# tdz.net
KiCad netlist of a schematic drawn in EAGLE
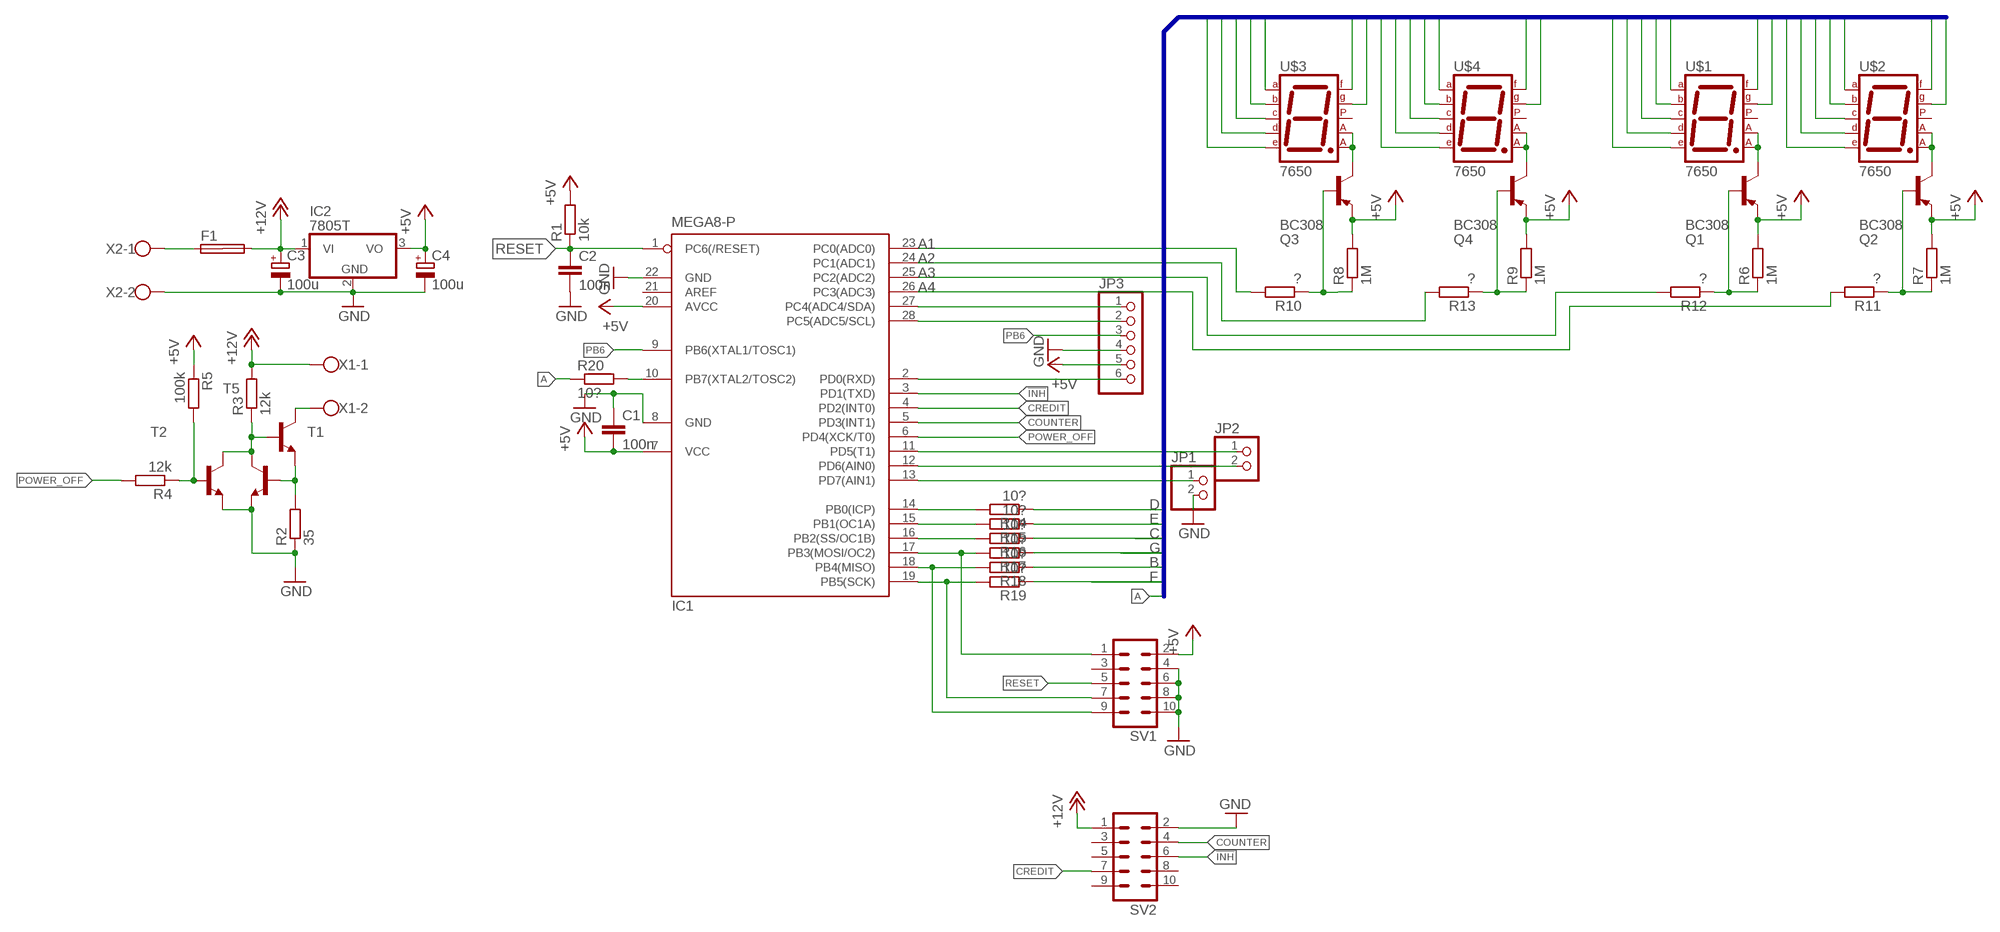
[diagram p0: schematic, sheet 1]

(export (version "E")
  (design (tool "Eeschema 10.0.6"))
  (components
    (comp (ref "C1")
      (value "100n")
      (footprint "eagle-import:C0603")
      (libsource (lib "eagle-import") (part "C-EUC0603"))
    )
    (comp (ref "C2")
      (value "100n")
      (footprint "eagle-import:C0603")
      (libsource (lib "eagle-import") (part "C-EUC0603"))
    )
    (comp (ref "C3")
      (value "100u")
      (footprint "eagle-import:E22-9")
      (libsource (lib "eagle-import") (part "CPOL-EUE22-9AXIAL"))
    )
    (comp (ref "C4")
      (value "100u")
      (footprint "eagle-import:E22-9")
      (libsource (lib "eagle-import") (part "CPOL-EUE22-9AXIAL"))
    )
    (comp (ref "F1")
      (value "SHK20Q")
      (footprint "eagle-import:SHK20Q")
      (libsource (lib "eagle-import") (part "SHK20Q"))
    )
    (comp (ref "IC1")
      (value "MEGA8-P")
      (footprint "eagle-import:DIL28-3")
      (libsource (lib "eagle-import") (part "MEGA8-P"))
    )
    (comp (ref "IC2")
      (value "7805T")
      (footprint "eagle-import:TO220H")
      (libsource (lib "eagle-import") (part "78T05"))
    )
    (comp (ref "JP1")
      (value "PINHD-1X02_2.54-S")
      (footprint "eagle-import:1X02-S")
      (libsource (lib "eagle-import") (part "PINHD-1X02_2.54-S"))
    )
    (comp (ref "JP2")
      (value "PINHD-1X02_2.54-S")
      (footprint "eagle-import:1X02-S")
      (libsource (lib "eagle-import") (part "PINHD-1X02_2.54-S"))
    )
    (comp (ref "JP3")
      (value "PINHD-1X6")
      (footprint "eagle-import:1X06")
      (libsource (lib "eagle-import") (part "PINHD-1X6"))
    )
    (comp (ref "Q1")
      (value "BC308")
      (footprint "eagle-import:TO92-EBC")
      (libsource (lib "eagle-import") (part "BCX79"))
    )
    (comp (ref "Q2")
      (value "BC308")
      (footprint "eagle-import:TO92-EBC")
      (libsource (lib "eagle-import") (part "BCX79"))
    )
    (comp (ref "Q3")
      (value "BC308")
      (footprint "eagle-import:TO92-EBC")
      (libsource (lib "eagle-import") (part "BCX79"))
    )
    (comp (ref "Q4")
      (value "BC308")
      (footprint "eagle-import:TO92-EBC")
      (libsource (lib "eagle-import") (part "BCX79"))
    )
    (comp (ref "R1")
      (value "10k")
      (footprint "eagle-import:R0603")
      (libsource (lib "eagle-import") (part "R-EU_R0603"))
    )
    (comp (ref "R2")
      (value "35")
      (footprint "eagle-import:R0603")
      (libsource (lib "eagle-import") (part "R-EU_R0603"))
    )
    (comp (ref "R3")
      (value "12k")
      (footprint "eagle-import:R0603")
      (libsource (lib "eagle-import") (part "R-EU_R0603"))
    )
    (comp (ref "R4")
      (value "12k")
      (footprint "eagle-import:R0603")
      (libsource (lib "eagle-import") (part "R-EU_R0603"))
    )
    (comp (ref "R5")
      (value "100k")
      (footprint "eagle-import:R0603")
      (libsource (lib "eagle-import") (part "R-EU_R0603"))
    )
    (comp (ref "R6")
      (value "1M")
      (footprint "eagle-import:R0603")
      (libsource (lib "eagle-import") (part "R-EU_R0603"))
    )
    (comp (ref "R7")
      (value "1M")
      (footprint "eagle-import:R0603")
      (libsource (lib "eagle-import") (part "R-EU_R0603"))
    )
    (comp (ref "R8")
      (value "1M")
      (footprint "eagle-import:R0603")
      (libsource (lib "eagle-import") (part "R-EU_R0603"))
    )
    (comp (ref "R9")
      (value "1M")
      (footprint "eagle-import:R0603")
      (libsource (lib "eagle-import") (part "R-EU_R0603"))
    )
    (comp (ref "R10")
      (value "?")
      (footprint "eagle-import:0207_7")
      (libsource (lib "eagle-import") (part "R-EU_0207/7"))
    )
    (comp (ref "R11")
      (value "?")
      (footprint "eagle-import:0207_7")
      (libsource (lib "eagle-import") (part "R-EU_0207/7"))
    )
    (comp (ref "R12")
      (value "?")
      (footprint "eagle-import:0207_7")
      (libsource (lib "eagle-import") (part "R-EU_0207/7"))
    )
    (comp (ref "R13")
      (value "?")
      (footprint "eagle-import:0207_7")
      (libsource (lib "eagle-import") (part "R-EU_0207/7"))
    )
    (comp (ref "R14")
      (value "10?")
      (footprint "eagle-import:R0603")
      (libsource (lib "eagle-import") (part "R-EU_R0603"))
    )
    (comp (ref "R15")
      (value "10?")
      (footprint "eagle-import:R0603")
      (libsource (lib "eagle-import") (part "R-EU_R0603"))
    )
    (comp (ref "R16")
      (value "10?")
      (footprint "eagle-import:R0603")
      (libsource (lib "eagle-import") (part "R-EU_R0603"))
    )
    (comp (ref "R17")
      (value "10?")
      (footprint "eagle-import:R0603")
      (libsource (lib "eagle-import") (part "R-EU_R0603"))
    )
    (comp (ref "R18")
      (value "10?")
      (footprint "eagle-import:R0603")
      (libsource (lib "eagle-import") (part "R-EU_R0603"))
    )
    (comp (ref "R19")
      (value "10?")
      (footprint "eagle-import:R0603")
      (libsource (lib "eagle-import") (part "R-EU_R0603"))
    )
    (comp (ref "R20")
      (value "10?")
      (footprint "eagle-import:R0603")
      (libsource (lib "eagle-import") (part "R-EU_R0603"))
    )
    (comp (ref "SV1")
      (value "ML10L")
      (footprint "eagle-import:ML10L")
      (libsource (lib "eagle-import") (part "ML10L"))
    )
    (comp (ref "SV2")
      (value "ML10L")
      (footprint "eagle-import:ML10L")
      (libsource (lib "eagle-import") (part "ML10L"))
    )
    (comp (ref "T1")
      (value "BC548-NPN-TO92-CBE")
      (footprint "eagle-import:TO92-CBE")
      (libsource (lib "eagle-import") (part "-NPN-TO92-CBEBC548"))
    )
    (comp (ref "T2")
      (value "BC548-NPN-TO92-CBE")
      (footprint "eagle-import:TO92-CBE")
      (libsource (lib "eagle-import") (part "-NPN-TO92-CBEBC548"))
    )
    (comp (ref "T5")
      (value "BC548-NPN-TO92-CBE")
      (footprint "eagle-import:TO92-CBE")
      (libsource (lib "eagle-import") (part "-NPN-TO92-CBEBC548"))
    )
    (comp (ref "U$1")
      (value "7650")
      (footprint "eagle-import:7650")
      (libsource (lib "eagle-import") (part "7650"))
    )
    (comp (ref "U$2")
      (value "7650")
      (footprint "eagle-import:7650")
      (libsource (lib "eagle-import") (part "7650"))
    )
    (comp (ref "U$3")
      (value "7650")
      (footprint "eagle-import:7650")
      (libsource (lib "eagle-import") (part "7650"))
    )
    (comp (ref "U$4")
      (value "7650")
      (footprint "eagle-import:7650")
      (libsource (lib "eagle-import") (part "7650"))
    )
    (comp (ref "X1")
      (value "W237-102")
      (footprint "eagle-import:W237-102")
      (libsource (lib "eagle-import") (part "W237-102"))
    )
    (comp (ref "X2")
      (value "W237-102")
      (footprint "eagle-import:W237-102")
      (libsource (lib "eagle-import") (part "W237-102"))
    )
  )
  (nets
    (net (code "1") (name "+5V") (class "Default")
      (node (ref "C1") (pin "2") (pinfunction "2_2") (pintype "passive"))
      (node (ref "C4") (pin "+") (pinfunction "+_+") (pintype "passive"))
      (node (ref "IC1") (pin "20") (pinfunction "AVCC_20") (pintype "power_in"))
      (node (ref "IC1") (pin "7") (pinfunction "VCC_7") (pintype "power_in"))
      (node (ref "IC2") (pin "3") (pinfunction "VO_3") (pintype "passive"))
      (node (ref "JP3") (pin "5") (pinfunction "5_5") (pintype "passive"))
      (node (ref "Q1") (pin "E") (pinfunction "E_E") (pintype "passive"))
      (node (ref "Q2") (pin "E") (pinfunction "E_E") (pintype "passive"))
      (node (ref "Q3") (pin "E") (pinfunction "E_E") (pintype "passive"))
      (node (ref "Q4") (pin "E") (pinfunction "E_E") (pintype "passive"))
      (node (ref "R1") (pin "2") (pinfunction "2_2") (pintype "passive"))
      (node (ref "R5") (pin "1") (pinfunction "1_1") (pintype "passive"))
      (node (ref "R6") (pin "2") (pinfunction "2_2") (pintype "passive"))
      (node (ref "R7") (pin "2") (pinfunction "2_2") (pintype "passive"))
      (node (ref "R8") (pin "2") (pinfunction "2_2") (pintype "passive"))
      (node (ref "R9") (pin "2") (pinfunction "2_2") (pintype "passive"))
      (node (ref "SV1") (pin "2") (pinfunction "2_2") (pintype "passive"))
    )
    (net (code "2") (name "+12V") (class "Default")
      (node (ref "C3") (pin "+") (pinfunction "+_+") (pintype "passive"))
      (node (ref "F1") (pin "2A") (pinfunction "2A_2A") (pintype "passive"))
      (node (ref "IC2") (pin "1") (pinfunction "VI_1") (pintype "input"))
      (node (ref "R3") (pin "2") (pinfunction "2_2") (pintype "passive"))
      (node (ref "SV2") (pin "1") (pinfunction "1_1") (pintype "passive"))
      (node (ref "X1") (pin "1") (pinfunction "KL_1") (pintype "passive"))
    )
    (net (code "3") (name "/A1") (class "Default")
      (node (ref "IC1") (pin "23") (pinfunction "PC0(ADC0)_23") (pintype "bidirectional"))
      (node (ref "R10") (pin "2") (pinfunction "2_2") (pintype "passive"))
    )
    (net (code "4") (name "/A2") (class "Default")
      (node (ref "IC1") (pin "24") (pinfunction "PC1(ADC1)_24") (pintype "bidirectional"))
      (node (ref "R13") (pin "2") (pinfunction "2_2") (pintype "passive"))
    )
    (net (code "5") (name "/A3") (class "Default")
      (node (ref "IC1") (pin "25") (pinfunction "PC2(ADC2)_25") (pintype "bidirectional"))
      (node (ref "R12") (pin "2") (pinfunction "2_2") (pintype "passive"))
    )
    (net (code "6") (name "/A4") (class "Default")
      (node (ref "IC1") (pin "26") (pinfunction "PC3(ADC3)_26") (pintype "bidirectional"))
      (node (ref "R11") (pin "2") (pinfunction "2_2") (pintype "passive"))
    )
    (net (code "7") (name "/B") (class "Default")
      (node (ref "R18") (pin "1") (pinfunction "1_1") (pintype "passive"))
      (node (ref "U$1") (pin "P$13") (pinfunction "B_P$13") (pintype "passive"))
      (node (ref "U$2") (pin "P$13") (pinfunction "B_P$13") (pintype "passive"))
      (node (ref "U$3") (pin "P$13") (pinfunction "B_P$13") (pintype "passive"))
      (node (ref "U$4") (pin "P$13") (pinfunction "B_P$13") (pintype "passive"))
    )
    (net (code "8") (name "/C") (class "Default")
      (node (ref "R16") (pin "1") (pinfunction "1_1") (pintype "passive"))
      (node (ref "U$1") (pin "P$10") (pinfunction "C_P$10") (pintype "passive"))
      (node (ref "U$2") (pin "P$10") (pinfunction "C_P$10") (pintype "passive"))
      (node (ref "U$3") (pin "P$10") (pinfunction "C_P$10") (pintype "passive"))
      (node (ref "U$4") (pin "P$10") (pinfunction "C_P$10") (pintype "passive"))
    )
    (net (code "9") (name "/D") (class "Default")
      (node (ref "R14") (pin "1") (pinfunction "1_1") (pintype "passive"))
      (node (ref "U$1") (pin "P$8") (pinfunction "D_P$8") (pintype "passive"))
      (node (ref "U$2") (pin "P$8") (pinfunction "D_P$8") (pintype "passive"))
      (node (ref "U$3") (pin "P$8") (pinfunction "D_P$8") (pintype "passive"))
      (node (ref "U$4") (pin "P$8") (pinfunction "D_P$8") (pintype "passive"))
    )
    (net (code "10") (name "/E") (class "Default")
      (node (ref "R15") (pin "1") (pinfunction "1_1") (pintype "passive"))
      (node (ref "U$1") (pin "P$7") (pinfunction "E_P$7") (pintype "passive"))
      (node (ref "U$2") (pin "P$7") (pinfunction "E_P$7") (pintype "passive"))
      (node (ref "U$3") (pin "P$7") (pinfunction "E_P$7") (pintype "passive"))
      (node (ref "U$4") (pin "P$7") (pinfunction "E_P$7") (pintype "passive"))
    )
    (net (code "11") (name "/F") (class "Default")
      (node (ref "R19") (pin "1") (pinfunction "1_1") (pintype "passive"))
      (node (ref "U$1") (pin "P$2") (pinfunction "F_P$2") (pintype "passive"))
      (node (ref "U$2") (pin "P$2") (pinfunction "F_P$2") (pintype "passive"))
      (node (ref "U$3") (pin "P$2") (pinfunction "F_P$2") (pintype "passive"))
      (node (ref "U$4") (pin "P$2") (pinfunction "F_P$2") (pintype "passive"))
    )
    (net (code "12") (name "/G") (class "Default")
      (node (ref "R17") (pin "1") (pinfunction "1_1") (pintype "passive"))
      (node (ref "U$1") (pin "P$11") (pinfunction "G_P$11") (pintype "passive"))
      (node (ref "U$2") (pin "P$11") (pinfunction "G_P$11") (pintype "passive"))
      (node (ref "U$3") (pin "P$11") (pinfunction "G_P$11") (pintype "passive"))
      (node (ref "U$4") (pin "P$11") (pinfunction "G_P$11") (pintype "passive"))
    )
    (net (code "13") (name "/~{INH}") (class "Default")
      (node (ref "IC1") (pin "3") (pinfunction "PD1(TXD)_3") (pintype "bidirectional"))
      (node (ref "SV2") (pin "6") (pinfunction "6_6") (pintype "passive"))
    )
    (net (code "14") (name "A") (class "Default")
      (node (ref "R20") (pin "1") (pinfunction "1_1") (pintype "passive"))
      (node (ref "U$1") (pin "P$1") (pinfunction "A_P$1") (pintype "passive"))
      (node (ref "U$2") (pin "P$1") (pinfunction "A_P$1") (pintype "passive"))
      (node (ref "U$3") (pin "P$1") (pinfunction "A_P$1") (pintype "passive"))
      (node (ref "U$4") (pin "P$1") (pinfunction "A_P$1") (pintype "passive"))
    )
    (net (code "15") (name "COUNTER") (class "Default")
      (node (ref "IC1") (pin "5") (pinfunction "PD3(INT1)_5") (pintype "bidirectional"))
      (node (ref "SV2") (pin "4") (pinfunction "4_4") (pintype "passive"))
    )
    (net (code "16") (name "CREDIT") (class "Default")
      (node (ref "IC1") (pin "4") (pinfunction "PD2(INT0)_4") (pintype "bidirectional"))
      (node (ref "SV2") (pin "7") (pinfunction "7_7") (pintype "passive"))
    )
    (net (code "17") (name "GND") (class "Default")
      (node (ref "C1") (pin "1") (pinfunction "1_1") (pintype "passive"))
      (node (ref "C2") (pin "2") (pinfunction "2_2") (pintype "passive"))
      (node (ref "C3") (pin "-") (pinfunction "-_-") (pintype "passive"))
      (node (ref "C4") (pin "-") (pinfunction "-_-") (pintype "passive"))
      (node (ref "IC1") (pin "22") (pinfunction "GND_22") (pintype "power_in"))
      (node (ref "IC1") (pin "8") (pinfunction "GND_8") (pintype "power_in"))
      (node (ref "IC2") (pin "2") (pinfunction "GND_2") (pintype "passive"))
      (node (ref "JP1") (pin "2") (pinfunction "2_2") (pintype "passive"))
      (node (ref "JP3") (pin "4") (pinfunction "4_4") (pintype "passive"))
      (node (ref "R2") (pin "1") (pinfunction "1_1") (pintype "passive"))
      (node (ref "SV1") (pin "10") (pinfunction "10_10") (pintype "passive"))
      (node (ref "SV1") (pin "4") (pinfunction "4_4") (pintype "passive"))
      (node (ref "SV1") (pin "6") (pinfunction "6_6") (pintype "passive"))
      (node (ref "SV1") (pin "8") (pinfunction "8_8") (pintype "passive"))
      (node (ref "SV2") (pin "2") (pinfunction "2_2") (pintype "passive"))
      (node (ref "T1") (pin "E") (pinfunction "E_E") (pintype "passive"))
      (node (ref "T2") (pin "E") (pinfunction "E_E") (pintype "passive"))
      (node (ref "X2") (pin "2") (pinfunction "KL_2") (pintype "passive"))
    )
    (net (code "18") (name "Net-(IC1-PB0(ICP))") (class "Default")
      (node (ref "IC1") (pin "14") (pinfunction "PB0(ICP)_14") (pintype "bidirectional"))
      (node (ref "R14") (pin "2") (pinfunction "2_2") (pintype "passive"))
    )
    (net (code "19") (name "Net-(IC1-PB1(OC1A))") (class "Default")
      (node (ref "IC1") (pin "15") (pinfunction "PB1(OC1A)_15") (pintype "bidirectional"))
      (node (ref "R15") (pin "2") (pinfunction "2_2") (pintype "passive"))
    )
    (net (code "20") (name "Net-(IC1-PB2(SS{slash}OC1B))") (class "Default")
      (node (ref "IC1") (pin "16") (pinfunction "PB2(SS/OC1B)_16") (pintype "bidirectional"))
      (node (ref "R16") (pin "2") (pinfunction "2_2") (pintype "passive"))
    )
    (net (code "21") (name "Net-(IC1-PB3(MOSI{slash}OC2))") (class "Default")
      (node (ref "IC1") (pin "17") (pinfunction "PB3(MOSI/OC2)_17") (pintype "bidirectional"))
      (node (ref "R17") (pin "2") (pinfunction "2_2") (pintype "passive"))
      (node (ref "SV1") (pin "1") (pinfunction "1_1") (pintype "passive"))
    )
    (net (code "22") (name "Net-(IC1-PB4(MISO))") (class "Default")
      (node (ref "IC1") (pin "18") (pinfunction "PB4(MISO)_18") (pintype "bidirectional"))
      (node (ref "R18") (pin "2") (pinfunction "2_2") (pintype "passive"))
      (node (ref "SV1") (pin "9") (pinfunction "9_9") (pintype "passive"))
    )
    (net (code "23") (name "Net-(IC1-PB5(SCK))") (class "Default")
      (node (ref "IC1") (pin "19") (pinfunction "PB5(SCK)_19") (pintype "bidirectional"))
      (node (ref "R19") (pin "2") (pinfunction "2_2") (pintype "passive"))
      (node (ref "SV1") (pin "7") (pinfunction "7_7") (pintype "passive"))
    )
    (net (code "24") (name "Net-(IC1-PB7(XTAL2{slash}TOSC2))") (class "Default")
      (node (ref "IC1") (pin "10") (pinfunction "PB7(XTAL2/TOSC2)_10") (pintype "bidirectional"))
      (node (ref "R20") (pin "2") (pinfunction "2_2") (pintype "passive"))
    )
    (net (code "25") (name "Net-(IC1-PC4(ADC4{slash}SDA))") (class "Default")
      (node (ref "IC1") (pin "27") (pinfunction "PC4(ADC4/SDA)_27") (pintype "bidirectional"))
      (node (ref "JP3") (pin "1") (pinfunction "1_1") (pintype "passive"))
    )
    (net (code "26") (name "Net-(IC1-PC5(ADC5{slash}SCL))") (class "Default")
      (node (ref "IC1") (pin "28") (pinfunction "PC5(ADC5/SCL)_28") (pintype "bidirectional"))
      (node (ref "JP3") (pin "2") (pinfunction "2_2") (pintype "passive"))
    )
    (net (code "27") (name "Net-(IC1-PD0(RXD))") (class "Default")
      (node (ref "IC1") (pin "2") (pinfunction "PD0(RXD)_2") (pintype "bidirectional"))
      (node (ref "JP3") (pin "6") (pinfunction "6_6") (pintype "passive"))
    )
    (net (code "28") (name "Net-(IC1-PD5(T1))") (class "Default")
      (node (ref "IC1") (pin "11") (pinfunction "PD5(T1)_11") (pintype "bidirectional"))
      (node (ref "JP2") (pin "1") (pinfunction "1_1") (pintype "passive"))
    )
    (net (code "29") (name "Net-(IC1-PD6(AIN0))") (class "Default")
      (node (ref "IC1") (pin "12") (pinfunction "PD6(AIN0)_12") (pintype "bidirectional"))
      (node (ref "JP2") (pin "2") (pinfunction "2_2") (pintype "passive"))
    )
    (net (code "30") (name "Net-(IC1-PD7(AIN1))") (class "Default")
      (node (ref "IC1") (pin "13") (pinfunction "PD7(AIN1)_13") (pintype "bidirectional"))
      (node (ref "JP1") (pin "1") (pinfunction "1_1") (pintype "passive"))
    )
    (net (code "31") (name "Net-(Q1-PadB)") (class "Default")
      (node (ref "Q1") (pin "B") (pinfunction "B_B") (pintype "passive"))
      (node (ref "R12") (pin "1") (pinfunction "1_1") (pintype "passive"))
      (node (ref "R6") (pin "1") (pinfunction "1_1") (pintype "passive"))
    )
    (net (code "32") (name "Net-(Q2-PadB)") (class "Default")
      (node (ref "Q2") (pin "B") (pinfunction "B_B") (pintype "passive"))
      (node (ref "R11") (pin "1") (pinfunction "1_1") (pintype "passive"))
      (node (ref "R7") (pin "1") (pinfunction "1_1") (pintype "passive"))
    )
    (net (code "33") (name "Net-(Q3-PadB)") (class "Default")
      (node (ref "Q3") (pin "B") (pinfunction "B_B") (pintype "passive"))
      (node (ref "R10") (pin "1") (pinfunction "1_1") (pintype "passive"))
      (node (ref "R8") (pin "1") (pinfunction "1_1") (pintype "passive"))
    )
    (net (code "34") (name "Net-(Q4-PadB)") (class "Default")
      (node (ref "Q4") (pin "B") (pinfunction "B_B") (pintype "passive"))
      (node (ref "R13") (pin "1") (pinfunction "1_1") (pintype "passive"))
      (node (ref "R9") (pin "1") (pinfunction "1_1") (pintype "passive"))
    )
    (net (code "35") (name "Net-(R2-Pad2)") (class "Default")
      (node (ref "R2") (pin "2") (pinfunction "2_2") (pintype "passive"))
      (node (ref "T1") (pin "B") (pinfunction "B_B") (pintype "passive"))
      (node (ref "T5") (pin "E") (pinfunction "E_E") (pintype "passive"))
    )
    (net (code "36") (name "Net-(R3-Pad1)") (class "Default")
      (node (ref "R3") (pin "1") (pinfunction "1_1") (pintype "passive"))
      (node (ref "T1") (pin "C") (pinfunction "C_C") (pintype "passive"))
      (node (ref "T2") (pin "C") (pinfunction "C_C") (pintype "passive"))
      (node (ref "T5") (pin "B") (pinfunction "B_B") (pintype "passive"))
    )
    (net (code "37") (name "Net-(R4-Pad1)") (class "Default")
      (node (ref "R4") (pin "1") (pinfunction "1_1") (pintype "passive"))
      (node (ref "R5") (pin "2") (pinfunction "2_2") (pintype "passive"))
      (node (ref "T2") (pin "B") (pinfunction "B_B") (pintype "passive"))
    )
    (net (code "38") (name "Net-(U$1-CA1)") (class "Default")
      (node (ref "Q1") (pin "C") (pinfunction "C_C") (pintype "passive"))
      (node (ref "U$1") (pin "P$14") (pinfunction "CA2_P$14") (pintype "passive"))
      (node (ref "U$1") (pin "P$3") (pinfunction "CA1_P$3") (pintype "passive"))
    )
    (net (code "39") (name "Net-(U$2-CA1)") (class "Default")
      (node (ref "Q2") (pin "C") (pinfunction "C_C") (pintype "passive"))
      (node (ref "U$2") (pin "P$14") (pinfunction "CA2_P$14") (pintype "passive"))
      (node (ref "U$2") (pin "P$3") (pinfunction "CA1_P$3") (pintype "passive"))
    )
    (net (code "40") (name "Net-(U$3-CA1)") (class "Default")
      (node (ref "Q3") (pin "C") (pinfunction "C_C") (pintype "passive"))
      (node (ref "U$3") (pin "P$14") (pinfunction "CA2_P$14") (pintype "passive"))
      (node (ref "U$3") (pin "P$3") (pinfunction "CA1_P$3") (pintype "passive"))
    )
    (net (code "41") (name "Net-(U$4-CA1)") (class "Default")
      (node (ref "Q4") (pin "C") (pinfunction "C_C") (pintype "passive"))
      (node (ref "U$4") (pin "P$14") (pinfunction "CA2_P$14") (pintype "passive"))
      (node (ref "U$4") (pin "P$3") (pinfunction "CA1_P$3") (pintype "passive"))
    )
    (net (code "42") (name "Net-(X1B-KL)") (class "Default")
      (node (ref "T5") (pin "C") (pinfunction "C_C") (pintype "passive"))
      (node (ref "X1") (pin "2") (pinfunction "KL_2") (pintype "passive"))
    )
    (net (code "43") (name "Net-(X2A-KL)") (class "Default")
      (node (ref "F1") (pin "1A") (pinfunction "1A_1A") (pintype "passive"))
      (node (ref "X2") (pin "1") (pinfunction "KL_1") (pintype "passive"))
    )
    (net (code "44") (name "PB6") (class "Default")
      (node (ref "IC1") (pin "9") (pinfunction "PB6(XTAL1/TOSC1)_9") (pintype "bidirectional"))
      (node (ref "JP3") (pin "3") (pinfunction "3_3") (pintype "passive"))
    )
    (net (code "45") (name "POWER_OFF") (class "Default")
      (node (ref "IC1") (pin "6") (pinfunction "PD4(XCK/T0)_6") (pintype "bidirectional"))
      (node (ref "R4") (pin "2") (pinfunction "2_2") (pintype "passive"))
    )
    (net (code "46") (name "RESET") (class "Default")
      (node (ref "C2") (pin "1") (pinfunction "1_1") (pintype "passive"))
      (node (ref "IC1") (pin "1") (pinfunction "PC6(/RESET)_1") (pintype "bidirectional"))
      (node (ref "R1") (pin "1") (pinfunction "1_1") (pintype "passive"))
      (node (ref "SV1") (pin "5") (pinfunction "5_5") (pintype "passive"))
    )
    (net (code "47") (name "unconnected-(F1-Pad1B)") (class "Default")
      (node (ref "F1") (pin "1B") (pinfunction "1B_1B") (pintype "passive"))
    )
    (net (code "48") (name "unconnected-(F1-Pad2B)") (class "Default")
      (node (ref "F1") (pin "2B") (pinfunction "2B_2B") (pintype "passive"))
    )
    (net (code "49") (name "unconnected-(IC1-AREF-Pad21)") (class "Default")
      (node (ref "IC1") (pin "21") (pinfunction "AREF_21") (pintype "passive"))
    )
    (net (code "50") (name "unconnected-(SV1-Pad3)") (class "Default")
      (node (ref "SV1") (pin "3") (pinfunction "3_3") (pintype "passive"))
    )
    (net (code "51") (name "unconnected-(SV2-Pad3)") (class "Default")
      (node (ref "SV2") (pin "3") (pinfunction "3_3") (pintype "passive"))
    )
    (net (code "52") (name "unconnected-(SV2-Pad5)") (class "Default")
      (node (ref "SV2") (pin "5") (pinfunction "5_5") (pintype "passive"))
    )
    (net (code "53") (name "unconnected-(SV2-Pad8)") (class "Default")
      (node (ref "SV2") (pin "8") (pinfunction "8_8") (pintype "passive"))
    )
    (net (code "54") (name "unconnected-(SV2-Pad9)") (class "Default")
      (node (ref "SV2") (pin "9") (pinfunction "9_9") (pintype "passive"))
    )
    (net (code "55") (name "unconnected-(SV2-Pad10)") (class "Default")
      (node (ref "SV2") (pin "10") (pinfunction "10_10") (pintype "passive"))
    )
    (net (code "56") (name "unconnected-(U$1-DP-PadP$6)") (class "Default")
      (node (ref "U$1") (pin "P$6") (pinfunction "DP_P$6") (pintype "passive"))
    )
    (net (code "57") (name "unconnected-(U$2-DP-PadP$6)") (class "Default")
      (node (ref "U$2") (pin "P$6") (pinfunction "DP_P$6") (pintype "passive"))
    )
    (net (code "58") (name "unconnected-(U$3-DP-PadP$6)") (class "Default")
      (node (ref "U$3") (pin "P$6") (pinfunction "DP_P$6") (pintype "passive"))
    )
    (net (code "59") (name "unconnected-(U$4-DP-PadP$6)") (class "Default")
      (node (ref "U$4") (pin "P$6") (pinfunction "DP_P$6") (pintype "passive"))
    )
  )
)
